# Transmitter.net
KiCad netlist of a schematic drawn in Altium Designer
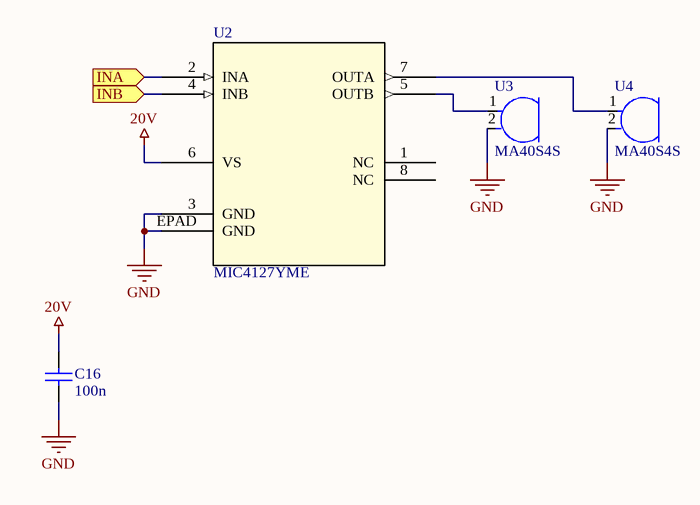
[diagram p0: Transmitter.SchDoc]

(export (version "E")
  (design (tool "Eeschema 10.0.6"))
  (components
    (comp (ref "C16")
      (value "100n")
      (footprint "SAMS-C0603-2_M")
      (description "Multi-layer Ceramic Capacitor, -55 to 125 degC, 2-Pin SMD (0603), RoHS, Tape and Reel")
      (fields (field (name "MANUFACTURER") "Samsung Electro-Mechanics"))
      (libsource (lib "Altium Content Vault") (part "CAP-NP-2"))
    )
    (comp (ref "U2")
      (value "MIC4127YME")
      (footprint "SOIC8_EQA_MCH")
      (description "No Description Available")
      (fields (field (name "COPYRIGHT") "Copyright (C) 2022 Ultra Librarian. All rights reserved."))
      (libsource (lib "MIC4127YME") (part "MIC4127YME"))
    )
    (comp (ref "U3")
      (value "MA40S4S")
      (footprint "FP-MA40S4S-MFG")
      (description "ULTRASONIC SENSOR TRANS 40KHZ")
      (libsource (lib "Altium Content Vault") (part "1b72337432ad8929c0ae54f99eb68d9"))
    )
    (comp (ref "U4")
      (value "MA40S4S")
      (footprint "FP-MA40S4S-MFG")
      (description "ULTRASONIC SENSOR TRANS 40KHZ")
      (libsource (lib "Altium Content Vault") (part "1b72337432ad8929c0ae54f99eb68d9"))
    )
  )
  (nets
    (net (code "1") (name "/INA") (class "Default")
      (node (ref "U2") (pin "2") (pinfunction "INA_2") (pintype "input"))
    )
    (net (code "2") (name "/INB") (class "Default")
      (node (ref "U2") (pin "4") (pinfunction "INB_4") (pintype "input"))
    )
    (net (code "3") (name "20V") (class "Default")
      (node (ref "C16") (pin "2") (pinfunction "2_2") (pintype "passive"))
      (node (ref "U2") (pin "6") (pinfunction "VS_6") (pintype "power_in"))
    )
    (net (code "4") (name "GND") (class "Default")
      (node (ref "C16") (pin "1") (pinfunction "1_1") (pintype "passive"))
      (node (ref "U2") (pin "3") (pinfunction "GND_3") (pintype "passive"))
      (node (ref "U2") (pin "EPAD") (pinfunction "GND_EPAD") (pintype "passive"))
      (node (ref "U3") (pin "2") (pinfunction "2_2") (pintype "passive"))
      (node (ref "U4") (pin "2") (pinfunction "2_2") (pintype "passive"))
    )
    (net (code "5") (name "Net-(U2-OUTA)") (class "Default")
      (node (ref "U2") (pin "7") (pinfunction "OUTA_7") (pintype "output"))
      (node (ref "U4") (pin "1") (pinfunction "1_1") (pintype "passive"))
    )
    (net (code "6") (name "Net-(U2-OUTB)") (class "Default")
      (node (ref "U2") (pin "5") (pinfunction "OUTB_5") (pintype "output"))
      (node (ref "U3") (pin "1") (pinfunction "1_1") (pintype "passive"))
    )
    (net (code "7") (name "unconnected-(U2-NC-Pad1)") (class "Default")
      (node (ref "U2") (pin "1") (pinfunction "NC_1") (pintype "passive"))
    )
    (net (code "8") (name "unconnected-(U2-NC-Pad8)") (class "Default")
      (node (ref "U2") (pin "8") (pinfunction "NC_8") (pintype "passive"))
    )
  )
)
